# power_tower_mast.net
KiCad netlist of a schematic drawn in EAGLE
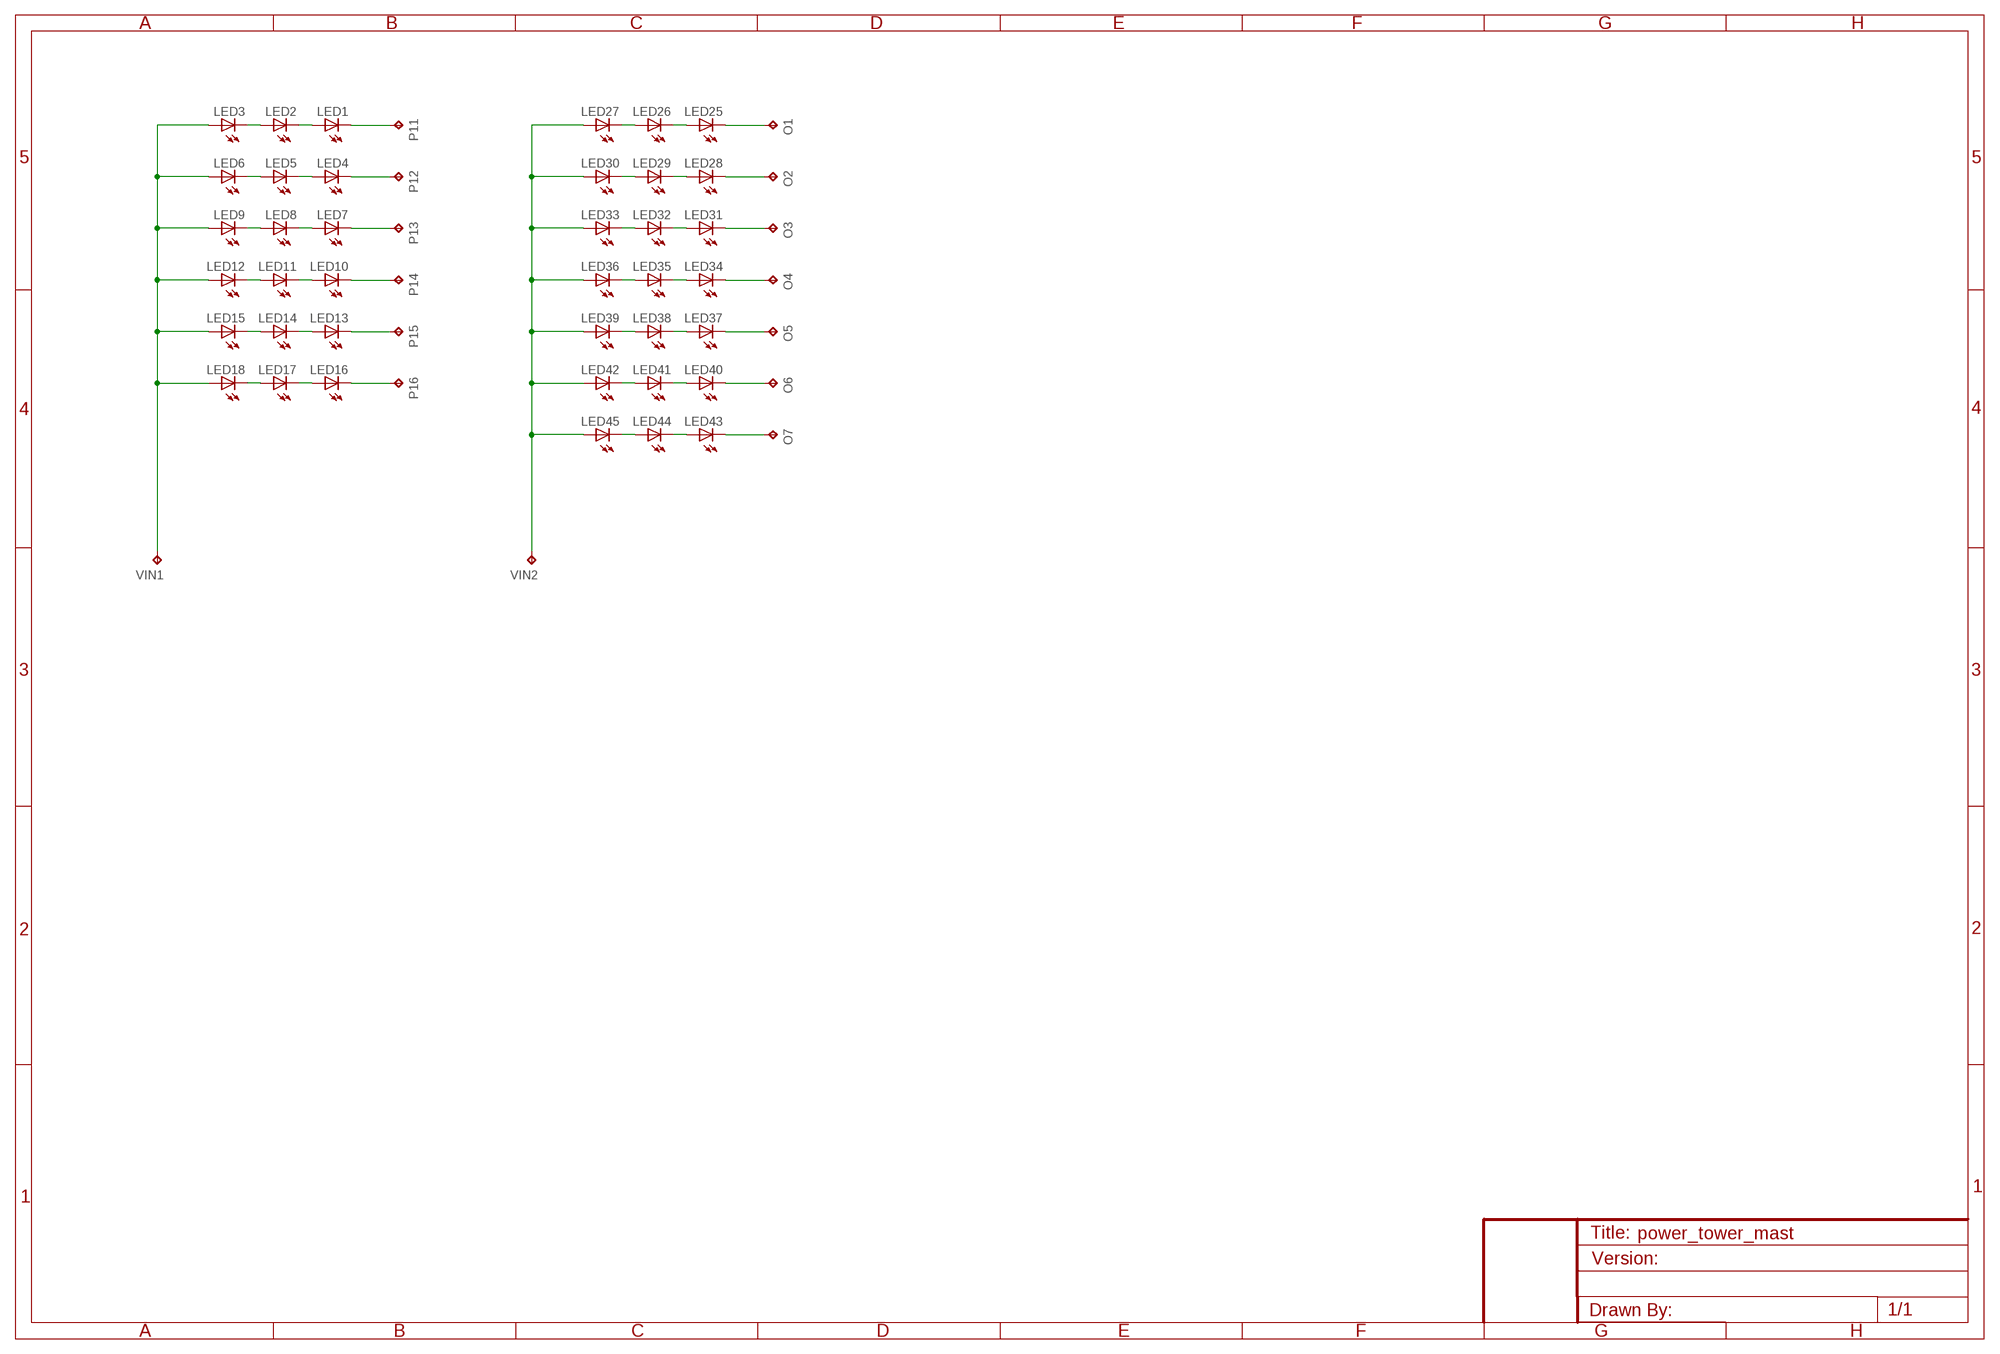
[diagram p0: schematic, sheet 1]

(export (version "E")
  (design (tool "Eeschema 10.0.6"))
  (components
    (comp (ref "LED1")
      (value "LED0805")
      (footprint "eagle-import:LED_0805")
      (libsource (lib "eagle-import") (part "LED0805"))
    )
    (comp (ref "LED2")
      (value "LED0805")
      (footprint "eagle-import:LED_0805")
      (libsource (lib "eagle-import") (part "LED0805"))
    )
    (comp (ref "LED3")
      (value "LED0805")
      (footprint "eagle-import:LED_0805")
      (libsource (lib "eagle-import") (part "LED0805"))
    )
    (comp (ref "LED4")
      (value "LED0805")
      (footprint "eagle-import:LED_0805")
      (libsource (lib "eagle-import") (part "LED0805"))
    )
    (comp (ref "LED5")
      (value "LED0805")
      (footprint "eagle-import:LED_0805")
      (libsource (lib "eagle-import") (part "LED0805"))
    )
    (comp (ref "LED6")
      (value "LED0805")
      (footprint "eagle-import:LED_0805")
      (libsource (lib "eagle-import") (part "LED0805"))
    )
    (comp (ref "LED7")
      (value "LED0805")
      (footprint "eagle-import:LED_0805")
      (libsource (lib "eagle-import") (part "LED0805"))
    )
    (comp (ref "LED8")
      (value "LED0805")
      (footprint "eagle-import:LED_0805")
      (libsource (lib "eagle-import") (part "LED0805"))
    )
    (comp (ref "LED9")
      (value "LED0805")
      (footprint "eagle-import:LED_0805")
      (libsource (lib "eagle-import") (part "LED0805"))
    )
    (comp (ref "LED10")
      (value "LED0805")
      (footprint "eagle-import:LED_0805")
      (libsource (lib "eagle-import") (part "LED0805"))
    )
    (comp (ref "LED11")
      (value "LED0805")
      (footprint "eagle-import:LED_0805")
      (libsource (lib "eagle-import") (part "LED0805"))
    )
    (comp (ref "LED12")
      (value "LED0805")
      (footprint "eagle-import:LED_0805")
      (libsource (lib "eagle-import") (part "LED0805"))
    )
    (comp (ref "LED13")
      (value "LED0805")
      (footprint "eagle-import:LED_0805")
      (libsource (lib "eagle-import") (part "LED0805"))
    )
    (comp (ref "LED14")
      (value "LED0805")
      (footprint "eagle-import:LED_0805")
      (libsource (lib "eagle-import") (part "LED0805"))
    )
    (comp (ref "LED15")
      (value "LED0805")
      (footprint "eagle-import:LED_0805")
      (libsource (lib "eagle-import") (part "LED0805"))
    )
    (comp (ref "LED16")
      (value "LED0805")
      (footprint "eagle-import:LED_0805")
      (libsource (lib "eagle-import") (part "LED0805"))
    )
    (comp (ref "LED17")
      (value "LED0805")
      (footprint "eagle-import:LED_0805")
      (libsource (lib "eagle-import") (part "LED0805"))
    )
    (comp (ref "LED18")
      (value "LED0805")
      (footprint "eagle-import:LED_0805")
      (libsource (lib "eagle-import") (part "LED0805"))
    )
    (comp (ref "LED25")
      (value "LED0805")
      (footprint "eagle-import:LED_0805")
      (libsource (lib "eagle-import") (part "LED0805"))
    )
    (comp (ref "LED26")
      (value "LED0805")
      (footprint "eagle-import:LED_0805")
      (libsource (lib "eagle-import") (part "LED0805"))
    )
    (comp (ref "LED27")
      (value "LED0805")
      (footprint "eagle-import:LED_0805")
      (libsource (lib "eagle-import") (part "LED0805"))
    )
    (comp (ref "LED28")
      (value "LED0805")
      (footprint "eagle-import:LED_0805")
      (libsource (lib "eagle-import") (part "LED0805"))
    )
    (comp (ref "LED29")
      (value "LED0805")
      (footprint "eagle-import:LED_0805")
      (libsource (lib "eagle-import") (part "LED0805"))
    )
    (comp (ref "LED30")
      (value "LED0805")
      (footprint "eagle-import:LED_0805")
      (libsource (lib "eagle-import") (part "LED0805"))
    )
    (comp (ref "LED31")
      (value "LED0805")
      (footprint "eagle-import:LED_0805")
      (libsource (lib "eagle-import") (part "LED0805"))
    )
    (comp (ref "LED32")
      (value "LED0805")
      (footprint "eagle-import:LED_0805")
      (libsource (lib "eagle-import") (part "LED0805"))
    )
    (comp (ref "LED33")
      (value "LED0805")
      (footprint "eagle-import:LED_0805")
      (libsource (lib "eagle-import") (part "LED0805"))
    )
    (comp (ref "LED34")
      (value "LED0805")
      (footprint "eagle-import:LED_0805")
      (libsource (lib "eagle-import") (part "LED0805"))
    )
    (comp (ref "LED35")
      (value "LED0805")
      (footprint "eagle-import:LED_0805")
      (libsource (lib "eagle-import") (part "LED0805"))
    )
    (comp (ref "LED36")
      (value "LED0805")
      (footprint "eagle-import:LED_0805")
      (libsource (lib "eagle-import") (part "LED0805"))
    )
    (comp (ref "LED37")
      (value "LED0805")
      (footprint "eagle-import:LED_0805")
      (libsource (lib "eagle-import") (part "LED0805"))
    )
    (comp (ref "LED38")
      (value "LED0805")
      (footprint "eagle-import:LED_0805")
      (libsource (lib "eagle-import") (part "LED0805"))
    )
    (comp (ref "LED39")
      (value "LED0805")
      (footprint "eagle-import:LED_0805")
      (libsource (lib "eagle-import") (part "LED0805"))
    )
    (comp (ref "LED40")
      (value "LED0805")
      (footprint "eagle-import:LED_0805")
      (libsource (lib "eagle-import") (part "LED0805"))
    )
    (comp (ref "LED41")
      (value "LED0805")
      (footprint "eagle-import:LED_0805")
      (libsource (lib "eagle-import") (part "LED0805"))
    )
    (comp (ref "LED42")
      (value "LED0805")
      (footprint "eagle-import:LED_0805")
      (libsource (lib "eagle-import") (part "LED0805"))
    )
    (comp (ref "LED43")
      (value "LED0805")
      (footprint "eagle-import:LED_0805")
      (libsource (lib "eagle-import") (part "LED0805"))
    )
    (comp (ref "LED44")
      (value "LED0805")
      (footprint "eagle-import:LED_0805")
      (libsource (lib "eagle-import") (part "LED0805"))
    )
    (comp (ref "LED45")
      (value "LED0805")
      (footprint "eagle-import:LED_0805")
      (libsource (lib "eagle-import") (part "LED0805"))
    )
    (comp (ref "O1")
      (value "TEST_POINTPAD1-20")
      (footprint "eagle-import:P1-20")
      (libsource (lib "eagle-import") (part "TEST_POINTPAD1-20"))
    )
    (comp (ref "O2")
      (value "TEST_POINTPAD1-20")
      (footprint "eagle-import:P1-20")
      (libsource (lib "eagle-import") (part "TEST_POINTPAD1-20"))
    )
    (comp (ref "O3")
      (value "TEST_POINTPAD1-20")
      (footprint "eagle-import:P1-20")
      (libsource (lib "eagle-import") (part "TEST_POINTPAD1-20"))
    )
    (comp (ref "O4")
      (value "TEST_POINTPAD1-20")
      (footprint "eagle-import:P1-20")
      (libsource (lib "eagle-import") (part "TEST_POINTPAD1-20"))
    )
    (comp (ref "O5")
      (value "TEST_POINTPAD1-20")
      (footprint "eagle-import:P1-20")
      (libsource (lib "eagle-import") (part "TEST_POINTPAD1-20"))
    )
    (comp (ref "O6")
      (value "TEST_POINTPAD1-20")
      (footprint "eagle-import:P1-20")
      (libsource (lib "eagle-import") (part "TEST_POINTPAD1-20"))
    )
    (comp (ref "O7")
      (value "TEST_POINTPAD1-20")
      (footprint "eagle-import:P1-20")
      (libsource (lib "eagle-import") (part "TEST_POINTPAD1-20"))
    )
    (comp (ref "P11")
      (value "TEST_POINTPAD1-20")
      (footprint "eagle-import:P1-20")
      (libsource (lib "eagle-import") (part "TEST_POINTPAD1-20"))
    )
    (comp (ref "P12")
      (value "TEST_POINTPAD1-20")
      (footprint "eagle-import:P1-20")
      (libsource (lib "eagle-import") (part "TEST_POINTPAD1-20"))
    )
    (comp (ref "P13")
      (value "TEST_POINTPAD1-20")
      (footprint "eagle-import:P1-20")
      (libsource (lib "eagle-import") (part "TEST_POINTPAD1-20"))
    )
    (comp (ref "P14")
      (value "TEST_POINTPAD1-20")
      (footprint "eagle-import:P1-20")
      (libsource (lib "eagle-import") (part "TEST_POINTPAD1-20"))
    )
    (comp (ref "P15")
      (value "TEST_POINTPAD1-20")
      (footprint "eagle-import:P1-20")
      (libsource (lib "eagle-import") (part "TEST_POINTPAD1-20"))
    )
    (comp (ref "P16")
      (value "TEST_POINTPAD1-20")
      (footprint "eagle-import:P1-20")
      (libsource (lib "eagle-import") (part "TEST_POINTPAD1-20"))
    )
    (comp (ref "VIN1")
      (value "TEST_POINTPAD1-20")
      (footprint "eagle-import:P1-20")
      (libsource (lib "eagle-import") (part "TEST_POINTPAD1-20"))
    )
    (comp (ref "VIN2")
      (value "TEST_POINTPAD1-20")
      (footprint "eagle-import:P1-20")
      (libsource (lib "eagle-import") (part "TEST_POINTPAD1-20"))
    )
  )
  (nets
    (net (code "1") (name "Net-(LED1-PadA)") (class "Default")
      (node (ref "LED1") (pin "A") (pinfunction "A_A") (pintype "passive"))
      (node (ref "LED2") (pin "C") (pinfunction "C_C") (pintype "passive"))
    )
    (net (code "2") (name "Net-(LED1-PadC)") (class "Default")
      (node (ref "LED1") (pin "C") (pinfunction "C_C") (pintype "passive"))
      (node (ref "P11") (pin "TP") (pinfunction "TP_TP") (pintype "input"))
    )
    (net (code "3") (name "Net-(LED2-PadA)") (class "Default")
      (node (ref "LED2") (pin "A") (pinfunction "A_A") (pintype "passive"))
      (node (ref "LED3") (pin "C") (pinfunction "C_C") (pintype "passive"))
    )
    (net (code "4") (name "Net-(LED4-PadA)") (class "Default")
      (node (ref "LED4") (pin "A") (pinfunction "A_A") (pintype "passive"))
      (node (ref "LED5") (pin "C") (pinfunction "C_C") (pintype "passive"))
    )
    (net (code "5") (name "Net-(LED4-PadC)") (class "Default")
      (node (ref "LED4") (pin "C") (pinfunction "C_C") (pintype "passive"))
      (node (ref "P12") (pin "TP") (pinfunction "TP_TP") (pintype "input"))
    )
    (net (code "6") (name "Net-(LED5-PadA)") (class "Default")
      (node (ref "LED5") (pin "A") (pinfunction "A_A") (pintype "passive"))
      (node (ref "LED6") (pin "C") (pinfunction "C_C") (pintype "passive"))
    )
    (net (code "7") (name "Net-(LED7-PadA)") (class "Default")
      (node (ref "LED7") (pin "A") (pinfunction "A_A") (pintype "passive"))
      (node (ref "LED8") (pin "C") (pinfunction "C_C") (pintype "passive"))
    )
    (net (code "8") (name "Net-(LED7-PadC)") (class "Default")
      (node (ref "LED7") (pin "C") (pinfunction "C_C") (pintype "passive"))
      (node (ref "P13") (pin "TP") (pinfunction "TP_TP") (pintype "input"))
    )
    (net (code "9") (name "Net-(LED8-PadA)") (class "Default")
      (node (ref "LED8") (pin "A") (pinfunction "A_A") (pintype "passive"))
      (node (ref "LED9") (pin "C") (pinfunction "C_C") (pintype "passive"))
    )
    (net (code "10") (name "Net-(LED10-PadA)") (class "Default")
      (node (ref "LED10") (pin "A") (pinfunction "A_A") (pintype "passive"))
      (node (ref "LED11") (pin "C") (pinfunction "C_C") (pintype "passive"))
    )
    (net (code "11") (name "Net-(LED10-PadC)") (class "Default")
      (node (ref "LED10") (pin "C") (pinfunction "C_C") (pintype "passive"))
      (node (ref "P14") (pin "TP") (pinfunction "TP_TP") (pintype "input"))
    )
    (net (code "12") (name "Net-(LED11-PadA)") (class "Default")
      (node (ref "LED11") (pin "A") (pinfunction "A_A") (pintype "passive"))
      (node (ref "LED12") (pin "C") (pinfunction "C_C") (pintype "passive"))
    )
    (net (code "13") (name "Net-(LED12-PadA)") (class "Default")
      (node (ref "LED12") (pin "A") (pinfunction "A_A") (pintype "passive"))
      (node (ref "LED15") (pin "A") (pinfunction "A_A") (pintype "passive"))
      (node (ref "LED18") (pin "A") (pinfunction "A_A") (pintype "passive"))
      (node (ref "LED3") (pin "A") (pinfunction "A_A") (pintype "passive"))
      (node (ref "LED6") (pin "A") (pinfunction "A_A") (pintype "passive"))
      (node (ref "LED9") (pin "A") (pinfunction "A_A") (pintype "passive"))
      (node (ref "VIN1") (pin "TP") (pinfunction "TP_TP") (pintype "input"))
    )
    (net (code "14") (name "Net-(LED13-PadA)") (class "Default")
      (node (ref "LED13") (pin "A") (pinfunction "A_A") (pintype "passive"))
      (node (ref "LED14") (pin "C") (pinfunction "C_C") (pintype "passive"))
    )
    (net (code "15") (name "Net-(LED13-PadC)") (class "Default")
      (node (ref "LED13") (pin "C") (pinfunction "C_C") (pintype "passive"))
      (node (ref "P15") (pin "TP") (pinfunction "TP_TP") (pintype "input"))
    )
    (net (code "16") (name "Net-(LED14-PadA)") (class "Default")
      (node (ref "LED14") (pin "A") (pinfunction "A_A") (pintype "passive"))
      (node (ref "LED15") (pin "C") (pinfunction "C_C") (pintype "passive"))
    )
    (net (code "17") (name "Net-(LED16-PadA)") (class "Default")
      (node (ref "LED16") (pin "A") (pinfunction "A_A") (pintype "passive"))
      (node (ref "LED17") (pin "C") (pinfunction "C_C") (pintype "passive"))
    )
    (net (code "18") (name "Net-(LED16-PadC)") (class "Default")
      (node (ref "LED16") (pin "C") (pinfunction "C_C") (pintype "passive"))
      (node (ref "P16") (pin "TP") (pinfunction "TP_TP") (pintype "input"))
    )
    (net (code "19") (name "Net-(LED17-PadA)") (class "Default")
      (node (ref "LED17") (pin "A") (pinfunction "A_A") (pintype "passive"))
      (node (ref "LED18") (pin "C") (pinfunction "C_C") (pintype "passive"))
    )
    (net (code "20") (name "Net-(LED25-PadA)") (class "Default")
      (node (ref "LED25") (pin "A") (pinfunction "A_A") (pintype "passive"))
      (node (ref "LED26") (pin "C") (pinfunction "C_C") (pintype "passive"))
    )
    (net (code "21") (name "Net-(LED25-PadC)") (class "Default")
      (node (ref "LED25") (pin "C") (pinfunction "C_C") (pintype "passive"))
      (node (ref "O1") (pin "TP") (pinfunction "TP_TP") (pintype "input"))
    )
    (net (code "22") (name "Net-(LED26-PadA)") (class "Default")
      (node (ref "LED26") (pin "A") (pinfunction "A_A") (pintype "passive"))
      (node (ref "LED27") (pin "C") (pinfunction "C_C") (pintype "passive"))
    )
    (net (code "23") (name "Net-(LED27-PadA)") (class "Default")
      (node (ref "LED27") (pin "A") (pinfunction "A_A") (pintype "passive"))
      (node (ref "LED30") (pin "A") (pinfunction "A_A") (pintype "passive"))
      (node (ref "LED33") (pin "A") (pinfunction "A_A") (pintype "passive"))
      (node (ref "LED36") (pin "A") (pinfunction "A_A") (pintype "passive"))
      (node (ref "LED39") (pin "A") (pinfunction "A_A") (pintype "passive"))
      (node (ref "LED42") (pin "A") (pinfunction "A_A") (pintype "passive"))
      (node (ref "LED45") (pin "A") (pinfunction "A_A") (pintype "passive"))
      (node (ref "VIN2") (pin "TP") (pinfunction "TP_TP") (pintype "input"))
    )
    (net (code "24") (name "Net-(LED28-PadA)") (class "Default")
      (node (ref "LED28") (pin "A") (pinfunction "A_A") (pintype "passive"))
      (node (ref "LED29") (pin "C") (pinfunction "C_C") (pintype "passive"))
    )
    (net (code "25") (name "Net-(LED28-PadC)") (class "Default")
      (node (ref "LED28") (pin "C") (pinfunction "C_C") (pintype "passive"))
      (node (ref "O2") (pin "TP") (pinfunction "TP_TP") (pintype "input"))
    )
    (net (code "26") (name "Net-(LED29-PadA)") (class "Default")
      (node (ref "LED29") (pin "A") (pinfunction "A_A") (pintype "passive"))
      (node (ref "LED30") (pin "C") (pinfunction "C_C") (pintype "passive"))
    )
    (net (code "27") (name "Net-(LED31-PadA)") (class "Default")
      (node (ref "LED31") (pin "A") (pinfunction "A_A") (pintype "passive"))
      (node (ref "LED32") (pin "C") (pinfunction "C_C") (pintype "passive"))
    )
    (net (code "28") (name "Net-(LED31-PadC)") (class "Default")
      (node (ref "LED31") (pin "C") (pinfunction "C_C") (pintype "passive"))
      (node (ref "O3") (pin "TP") (pinfunction "TP_TP") (pintype "input"))
    )
    (net (code "29") (name "Net-(LED32-PadA)") (class "Default")
      (node (ref "LED32") (pin "A") (pinfunction "A_A") (pintype "passive"))
      (node (ref "LED33") (pin "C") (pinfunction "C_C") (pintype "passive"))
    )
    (net (code "30") (name "Net-(LED34-PadA)") (class "Default")
      (node (ref "LED34") (pin "A") (pinfunction "A_A") (pintype "passive"))
      (node (ref "LED35") (pin "C") (pinfunction "C_C") (pintype "passive"))
    )
    (net (code "31") (name "Net-(LED34-PadC)") (class "Default")
      (node (ref "LED34") (pin "C") (pinfunction "C_C") (pintype "passive"))
      (node (ref "O4") (pin "TP") (pinfunction "TP_TP") (pintype "input"))
    )
    (net (code "32") (name "Net-(LED35-PadA)") (class "Default")
      (node (ref "LED35") (pin "A") (pinfunction "A_A") (pintype "passive"))
      (node (ref "LED36") (pin "C") (pinfunction "C_C") (pintype "passive"))
    )
    (net (code "33") (name "Net-(LED37-PadA)") (class "Default")
      (node (ref "LED37") (pin "A") (pinfunction "A_A") (pintype "passive"))
      (node (ref "LED38") (pin "C") (pinfunction "C_C") (pintype "passive"))
    )
    (net (code "34") (name "Net-(LED37-PadC)") (class "Default")
      (node (ref "LED37") (pin "C") (pinfunction "C_C") (pintype "passive"))
      (node (ref "O5") (pin "TP") (pinfunction "TP_TP") (pintype "input"))
    )
    (net (code "35") (name "Net-(LED38-PadA)") (class "Default")
      (node (ref "LED38") (pin "A") (pinfunction "A_A") (pintype "passive"))
      (node (ref "LED39") (pin "C") (pinfunction "C_C") (pintype "passive"))
    )
    (net (code "36") (name "Net-(LED40-PadA)") (class "Default")
      (node (ref "LED40") (pin "A") (pinfunction "A_A") (pintype "passive"))
      (node (ref "LED41") (pin "C") (pinfunction "C_C") (pintype "passive"))
    )
    (net (code "37") (name "Net-(LED40-PadC)") (class "Default")
      (node (ref "LED40") (pin "C") (pinfunction "C_C") (pintype "passive"))
      (node (ref "O6") (pin "TP") (pinfunction "TP_TP") (pintype "input"))
    )
    (net (code "38") (name "Net-(LED41-PadA)") (class "Default")
      (node (ref "LED41") (pin "A") (pinfunction "A_A") (pintype "passive"))
      (node (ref "LED42") (pin "C") (pinfunction "C_C") (pintype "passive"))
    )
    (net (code "39") (name "Net-(LED43-PadA)") (class "Default")
      (node (ref "LED43") (pin "A") (pinfunction "A_A") (pintype "passive"))
      (node (ref "LED44") (pin "C") (pinfunction "C_C") (pintype "passive"))
    )
    (net (code "40") (name "Net-(LED43-PadC)") (class "Default")
      (node (ref "LED43") (pin "C") (pinfunction "C_C") (pintype "passive"))
      (node (ref "O7") (pin "TP") (pinfunction "TP_TP") (pintype "input"))
    )
    (net (code "41") (name "Net-(LED44-PadA)") (class "Default")
      (node (ref "LED44") (pin "A") (pinfunction "A_A") (pintype "passive"))
      (node (ref "LED45") (pin "C") (pinfunction "C_C") (pintype "passive"))
    )
  )
)
